# Adder.net
KiCad netlist of a schematic drawn in EAGLE
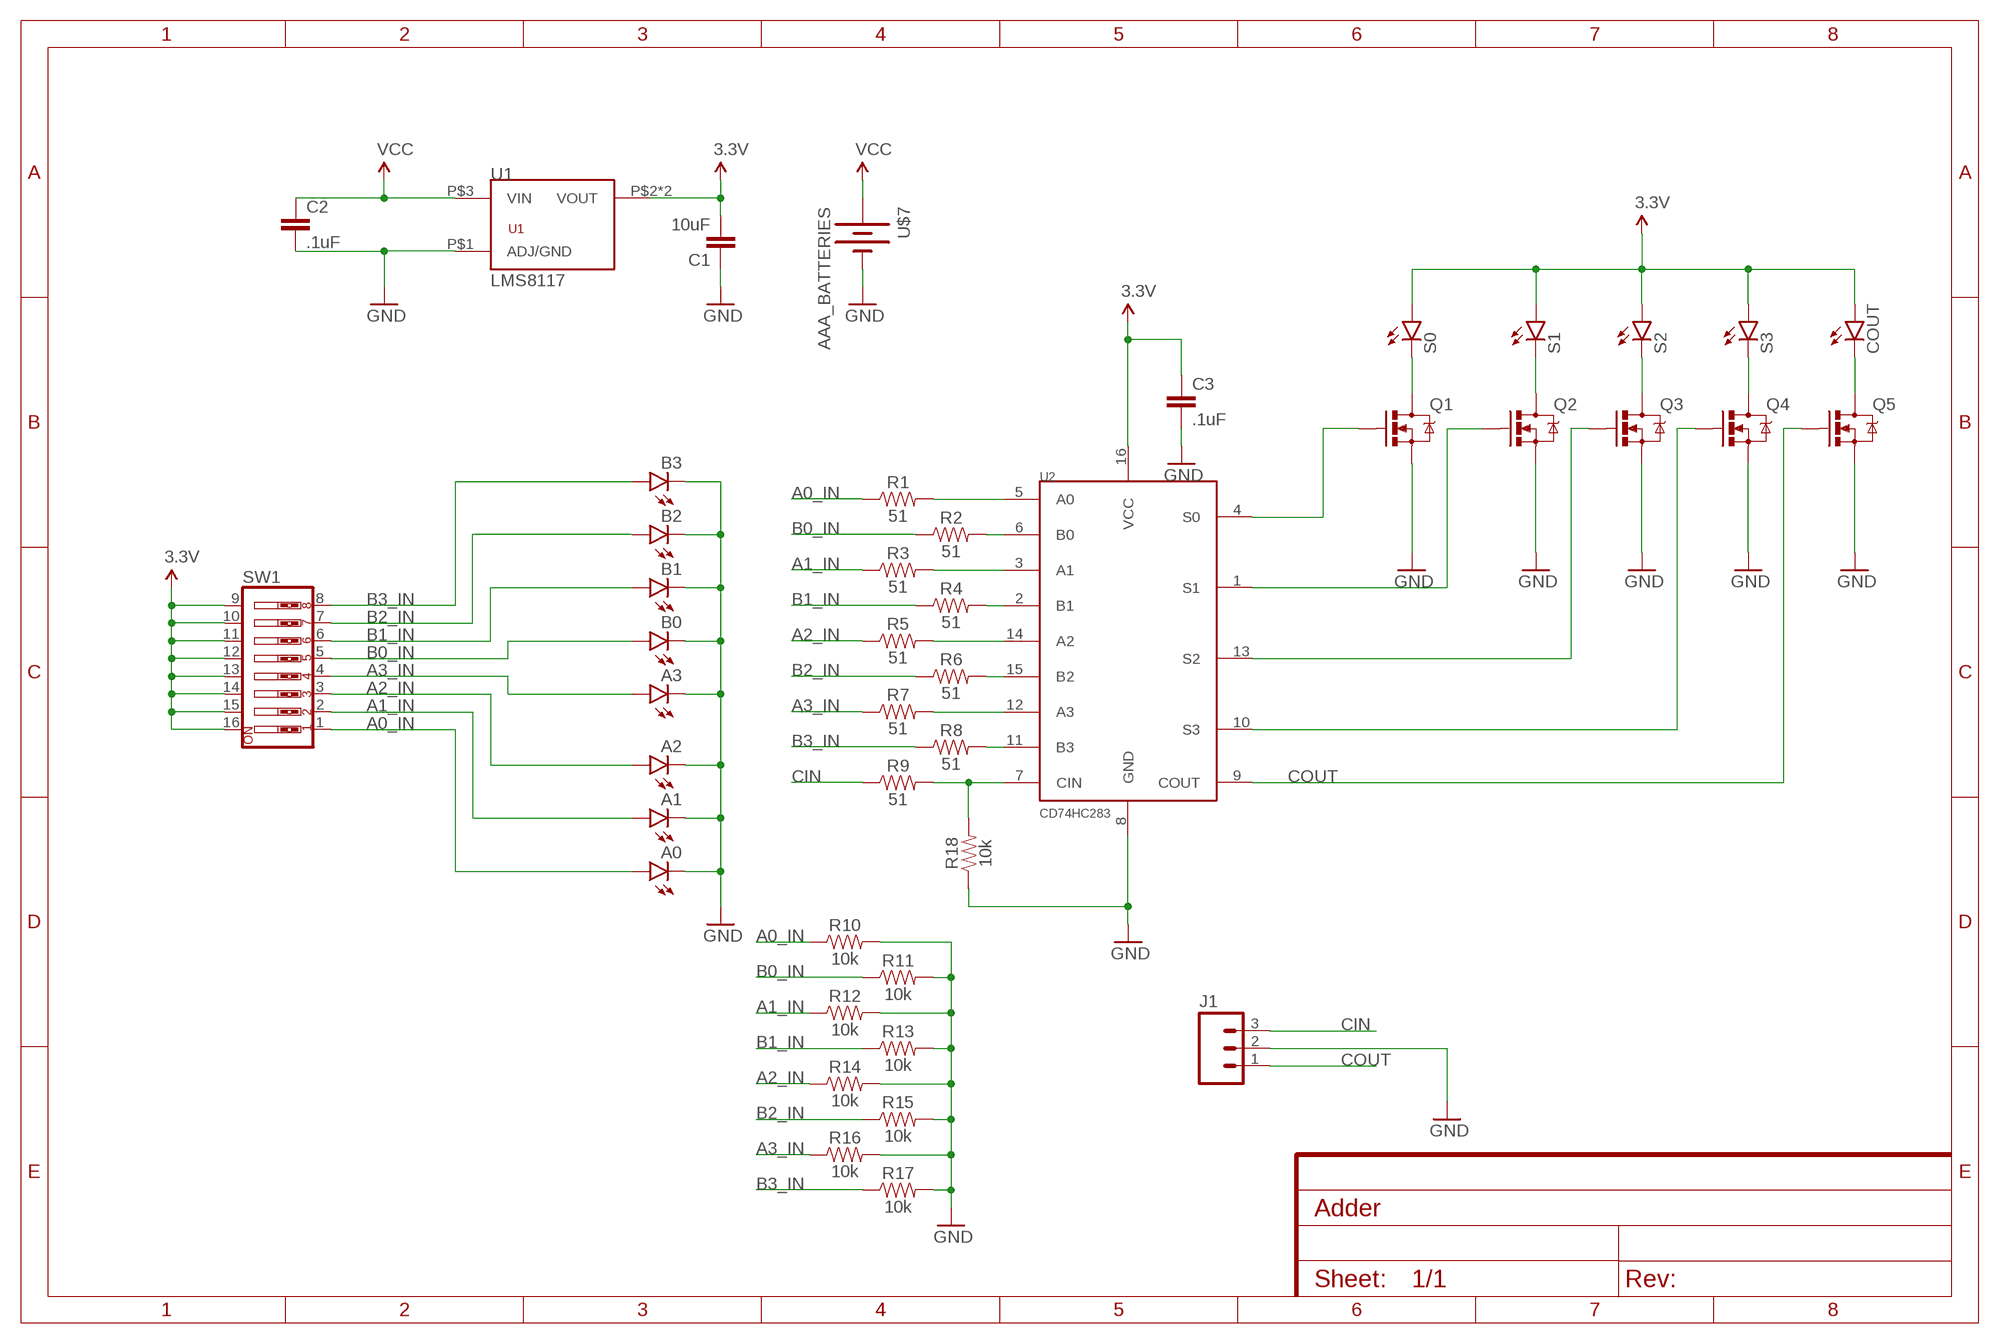
[diagram p0: schematic, sheet 1]

(export (version "E")
  (design (tool "Eeschema 10.0.6"))
  (components
    (comp (ref "A0")
      (value "LED5MM")
      (footprint "eagle-import:LED5MM")
      (libsource (lib "eagle-import") (part "LED5MM"))
    )
    (comp (ref "A1")
      (value "LED5MM")
      (footprint "eagle-import:LED5MM")
      (libsource (lib "eagle-import") (part "LED5MM"))
    )
    (comp (ref "A2")
      (value "LED5MM")
      (footprint "eagle-import:LED5MM")
      (libsource (lib "eagle-import") (part "LED5MM"))
    )
    (comp (ref "A3")
      (value "LED5MM")
      (footprint "eagle-import:LED5MM")
      (libsource (lib "eagle-import") (part "LED5MM"))
    )
    (comp (ref "B0")
      (value "LED5MM")
      (footprint "eagle-import:LED5MM")
      (libsource (lib "eagle-import") (part "LED5MM"))
    )
    (comp (ref "B1")
      (value "LED5MM")
      (footprint "eagle-import:LED5MM")
      (libsource (lib "eagle-import") (part "LED5MM"))
    )
    (comp (ref "B2")
      (value "LED5MM")
      (footprint "eagle-import:LED5MM")
      (libsource (lib "eagle-import") (part "LED5MM"))
    )
    (comp (ref "B3")
      (value "LED5MM")
      (footprint "eagle-import:LED5MM")
      (libsource (lib "eagle-import") (part "LED5MM"))
    )
    (comp (ref "C1")
      (value "10uF")
      (footprint "eagle-import:0603-CAP")
      (libsource (lib "eagle-import") (part "CAP0603-CAP"))
    )
    (comp (ref "C2")
      (value ".1uF")
      (footprint "eagle-import:0603-CAP")
      (libsource (lib "eagle-import") (part "CAP0603-CAP"))
    )
    (comp (ref "C3")
      (value ".1uF")
      (footprint "eagle-import:0603-CAP")
      (libsource (lib "eagle-import") (part "CAP0603-CAP"))
    )
    (comp (ref "COUT")
      (value "LED5MM")
      (footprint "eagle-import:LED5MM")
      (libsource (lib "eagle-import") (part "LED5MM"))
    )
    (comp (ref "J1")
      (value "M03PTH")
      (footprint "eagle-import:1X03")
      (libsource (lib "eagle-import") (part "M03PTH"))
    )
    (comp (ref "Q1")
      (value "MOSFET-NCHANNEL2N7000")
      (footprint "eagle-import:TO-92")
      (libsource (lib "eagle-import") (part "MOSFET-NCHANNEL2N7000"))
    )
    (comp (ref "Q2")
      (value "MOSFET-NCHANNEL2N7000")
      (footprint "eagle-import:TO-92")
      (libsource (lib "eagle-import") (part "MOSFET-NCHANNEL2N7000"))
    )
    (comp (ref "Q3")
      (value "MOSFET-NCHANNEL2N7000")
      (footprint "eagle-import:TO-92")
      (libsource (lib "eagle-import") (part "MOSFET-NCHANNEL2N7000"))
    )
    (comp (ref "Q4")
      (value "MOSFET-NCHANNEL2N7000")
      (footprint "eagle-import:TO-92")
      (libsource (lib "eagle-import") (part "MOSFET-NCHANNEL2N7000"))
    )
    (comp (ref "Q5")
      (value "MOSFET-NCHANNEL2N7000")
      (footprint "eagle-import:TO-92")
      (libsource (lib "eagle-import") (part "MOSFET-NCHANNEL2N7000"))
    )
    (comp (ref "R1")
      (value "51")
      (footprint "eagle-import:0805")
      (libsource (lib "eagle-import") (part "RESISTOR0805"))
    )
    (comp (ref "R2")
      (value "51")
      (footprint "eagle-import:0805")
      (libsource (lib "eagle-import") (part "RESISTOR0805"))
    )
    (comp (ref "R3")
      (value "51")
      (footprint "eagle-import:0805")
      (libsource (lib "eagle-import") (part "RESISTOR0805"))
    )
    (comp (ref "R4")
      (value "51")
      (footprint "eagle-import:0805")
      (libsource (lib "eagle-import") (part "RESISTOR0805"))
    )
    (comp (ref "R5")
      (value "51")
      (footprint "eagle-import:0805")
      (libsource (lib "eagle-import") (part "RESISTOR0805"))
    )
    (comp (ref "R6")
      (value "51")
      (footprint "eagle-import:0805")
      (libsource (lib "eagle-import") (part "RESISTOR0805"))
    )
    (comp (ref "R7")
      (value "51")
      (footprint "eagle-import:0805")
      (libsource (lib "eagle-import") (part "RESISTOR0805"))
    )
    (comp (ref "R8")
      (value "51")
      (footprint "eagle-import:0805")
      (libsource (lib "eagle-import") (part "RESISTOR0805"))
    )
    (comp (ref "R9")
      (value "51")
      (footprint "eagle-import:0805")
      (libsource (lib "eagle-import") (part "RESISTOR0805"))
    )
    (comp (ref "R10")
      (value "10k")
      (footprint "eagle-import:0805")
      (libsource (lib "eagle-import") (part "RESISTOR0805"))
    )
    (comp (ref "R11")
      (value "10k")
      (footprint "eagle-import:0805")
      (libsource (lib "eagle-import") (part "RESISTOR0805"))
    )
    (comp (ref "R12")
      (value "10k")
      (footprint "eagle-import:0805")
      (libsource (lib "eagle-import") (part "RESISTOR0805"))
    )
    (comp (ref "R13")
      (value "10k")
      (footprint "eagle-import:0805")
      (libsource (lib "eagle-import") (part "RESISTOR0805"))
    )
    (comp (ref "R14")
      (value "10k")
      (footprint "eagle-import:0805")
      (libsource (lib "eagle-import") (part "RESISTOR0805"))
    )
    (comp (ref "R15")
      (value "10k")
      (footprint "eagle-import:0805")
      (libsource (lib "eagle-import") (part "RESISTOR0805"))
    )
    (comp (ref "R16")
      (value "10k")
      (footprint "eagle-import:0805")
      (libsource (lib "eagle-import") (part "RESISTOR0805"))
    )
    (comp (ref "R17")
      (value "10k")
      (footprint "eagle-import:0805")
      (libsource (lib "eagle-import") (part "RESISTOR0805"))
    )
    (comp (ref "R18")
      (value "10k")
      (footprint "eagle-import:0805")
      (libsource (lib "eagle-import") (part "RESISTOR0805"))
    )
    (comp (ref "S0")
      (value "LED5MM")
      (footprint "eagle-import:LED5MM")
      (libsource (lib "eagle-import") (part "LED5MM"))
    )
    (comp (ref "S1")
      (value "LED5MM")
      (footprint "eagle-import:LED5MM")
      (libsource (lib "eagle-import") (part "LED5MM"))
    )
    (comp (ref "S2")
      (value "LED5MM")
      (footprint "eagle-import:LED5MM")
      (libsource (lib "eagle-import") (part "LED5MM"))
    )
    (comp (ref "S3")
      (value "LED5MM")
      (footprint "eagle-import:LED5MM")
      (libsource (lib "eagle-import") (part "LED5MM"))
    )
    (comp (ref "SW1")
      (value "SW_DIP-8")
      (footprint "eagle-import:DIPSWITCH-08")
      (libsource (lib "eagle-import") (part "SW_DIP-8"))
    )
    (comp (ref "U$7")
      (value "AAA_BATTERIES")
      (footprint "eagle-import:WIRE_LEADS")
      (libsource (lib "eagle-import") (part "AAA_BATTERIES"))
    )
    (comp (ref "U1")
      (value "LMS8117")
      (footprint "eagle-import:SOT-223")
      (libsource (lib "eagle-import") (part "LMS8117"))
    )
    (comp (ref "U2")
      (value "CD74HC283")
      (footprint "eagle-import:SO016")
      (libsource (lib "eagle-import") (part "CD74HC283"))
    )
  )
  (nets
    (net (code "1") (name "/A0_IN") (class "Default")
      (node (ref "A0") (pin "A") (pinfunction "A_A") (pintype "passive"))
      (node (ref "R1") (pin "1") (pinfunction "1_1") (pintype "passive"))
      (node (ref "R10") (pin "1") (pinfunction "1_1") (pintype "passive"))
      (node (ref "SW1") (pin "1") (pinfunction "1_1") (pintype "passive"))
    )
    (net (code "2") (name "/A1_IN") (class "Default")
      (node (ref "A1") (pin "A") (pinfunction "A_A") (pintype "passive"))
      (node (ref "R12") (pin "1") (pinfunction "1_1") (pintype "passive"))
      (node (ref "R3") (pin "1") (pinfunction "1_1") (pintype "passive"))
      (node (ref "SW1") (pin "2") (pinfunction "2_2") (pintype "passive"))
    )
    (net (code "3") (name "/A2_IN") (class "Default")
      (node (ref "A2") (pin "A") (pinfunction "A_A") (pintype "passive"))
      (node (ref "R14") (pin "1") (pinfunction "1_1") (pintype "passive"))
      (node (ref "R5") (pin "1") (pinfunction "1_1") (pintype "passive"))
      (node (ref "SW1") (pin "3") (pinfunction "3_3") (pintype "passive"))
    )
    (net (code "4") (name "/A3_IN") (class "Default")
      (node (ref "A3") (pin "A") (pinfunction "A_A") (pintype "passive"))
      (node (ref "R16") (pin "1") (pinfunction "1_1") (pintype "passive"))
      (node (ref "R7") (pin "1") (pinfunction "1_1") (pintype "passive"))
      (node (ref "SW1") (pin "4") (pinfunction "4_4") (pintype "passive"))
    )
    (net (code "5") (name "/B0_IN") (class "Default")
      (node (ref "B0") (pin "A") (pinfunction "A_A") (pintype "passive"))
      (node (ref "R11") (pin "1") (pinfunction "1_1") (pintype "passive"))
      (node (ref "R2") (pin "1") (pinfunction "1_1") (pintype "passive"))
      (node (ref "SW1") (pin "5") (pinfunction "5_5") (pintype "passive"))
    )
    (net (code "6") (name "/B1_IN") (class "Default")
      (node (ref "B1") (pin "A") (pinfunction "A_A") (pintype "passive"))
      (node (ref "R13") (pin "1") (pinfunction "1_1") (pintype "passive"))
      (node (ref "R4") (pin "1") (pinfunction "1_1") (pintype "passive"))
      (node (ref "SW1") (pin "6") (pinfunction "6_6") (pintype "passive"))
    )
    (net (code "7") (name "/B2_IN") (class "Default")
      (node (ref "B2") (pin "A") (pinfunction "A_A") (pintype "passive"))
      (node (ref "R15") (pin "1") (pinfunction "1_1") (pintype "passive"))
      (node (ref "R6") (pin "1") (pinfunction "1_1") (pintype "passive"))
      (node (ref "SW1") (pin "7") (pinfunction "7_7") (pintype "passive"))
    )
    (net (code "8") (name "/B3_IN") (class "Default")
      (node (ref "B3") (pin "A") (pinfunction "A_A") (pintype "passive"))
      (node (ref "R17") (pin "1") (pinfunction "1_1") (pintype "passive"))
      (node (ref "R8") (pin "1") (pinfunction "1_1") (pintype "passive"))
      (node (ref "SW1") (pin "8") (pinfunction "8_8") (pintype "passive"))
    )
    (net (code "9") (name "/CIN") (class "Default")
      (node (ref "J1") (pin "3") (pinfunction "3_3") (pintype "passive"))
      (node (ref "R9") (pin "1") (pinfunction "1_1") (pintype "passive"))
    )
    (net (code "10") (name "/COUT") (class "Default")
      (node (ref "J1") (pin "1") (pinfunction "1_1") (pintype "passive"))
      (node (ref "Q5") (pin "2") (pinfunction "G_2") (pintype "passive"))
      (node (ref "U2") (pin "9") (pinfunction "COUT_9") (pintype "bidirectional"))
    )
    (net (code "11") (name "3.3V") (class "Default")
      (node (ref "C1") (pin "2") (pinfunction "2_2") (pintype "passive"))
      (node (ref "C3") (pin "1") (pinfunction "1_1") (pintype "passive"))
      (node (ref "COUT") (pin "A") (pinfunction "A_A") (pintype "passive"))
      (node (ref "S0") (pin "A") (pinfunction "A_A") (pintype "passive"))
      (node (ref "S1") (pin "A") (pinfunction "A_A") (pintype "passive"))
      (node (ref "S2") (pin "A") (pinfunction "A_A") (pintype "passive"))
      (node (ref "S3") (pin "A") (pinfunction "A_A") (pintype "passive"))
      (node (ref "SW1") (pin "10") (pinfunction "10_10") (pintype "passive"))
      (node (ref "SW1") (pin "11") (pinfunction "11_11") (pintype "passive"))
      (node (ref "SW1") (pin "12") (pinfunction "12_12") (pintype "passive"))
      (node (ref "SW1") (pin "13") (pinfunction "13_13") (pintype "passive"))
      (node (ref "SW1") (pin "14") (pinfunction "14_14") (pintype "passive"))
      (node (ref "SW1") (pin "15") (pinfunction "15_15") (pintype "passive"))
      (node (ref "SW1") (pin "16") (pinfunction "16_16") (pintype "passive"))
      (node (ref "SW1") (pin "9") (pinfunction "9_9") (pintype "passive"))
      (node (ref "U1") (pin "P$2") (pinfunction "VOUT_P$2") (pintype "bidirectional"))
      (node (ref "U1") (pin "P$4") (pinfunction "VOUT_P$4") (pintype "bidirectional"))
      (node (ref "U2") (pin "16") (pinfunction "VCC_16") (pintype "bidirectional"))
    )
    (net (code "12") (name "GND") (class "Default")
      (node (ref "A0") (pin "K") (pinfunction "C_K") (pintype "passive"))
      (node (ref "A1") (pin "K") (pinfunction "C_K") (pintype "passive"))
      (node (ref "A2") (pin "K") (pinfunction "C_K") (pintype "passive"))
      (node (ref "A3") (pin "K") (pinfunction "C_K") (pintype "passive"))
      (node (ref "B0") (pin "K") (pinfunction "C_K") (pintype "passive"))
      (node (ref "B1") (pin "K") (pinfunction "C_K") (pintype "passive"))
      (node (ref "B2") (pin "K") (pinfunction "C_K") (pintype "passive"))
      (node (ref "B3") (pin "K") (pinfunction "C_K") (pintype "passive"))
      (node (ref "C1") (pin "1") (pinfunction "1_1") (pintype "passive"))
      (node (ref "C2") (pin "2") (pinfunction "2_2") (pintype "passive"))
      (node (ref "C3") (pin "2") (pinfunction "2_2") (pintype "passive"))
      (node (ref "J1") (pin "2") (pinfunction "2_2") (pintype "passive"))
      (node (ref "Q1") (pin "1") (pinfunction "S_1") (pintype "passive"))
      (node (ref "Q2") (pin "1") (pinfunction "S_1") (pintype "passive"))
      (node (ref "Q3") (pin "1") (pinfunction "S_1") (pintype "passive"))
      (node (ref "Q4") (pin "1") (pinfunction "S_1") (pintype "passive"))
      (node (ref "Q5") (pin "1") (pinfunction "S_1") (pintype "passive"))
      (node (ref "R10") (pin "2") (pinfunction "2_2") (pintype "passive"))
      (node (ref "R11") (pin "2") (pinfunction "2_2") (pintype "passive"))
      (node (ref "R12") (pin "2") (pinfunction "2_2") (pintype "passive"))
      (node (ref "R13") (pin "2") (pinfunction "2_2") (pintype "passive"))
      (node (ref "R14") (pin "2") (pinfunction "2_2") (pintype "passive"))
      (node (ref "R15") (pin "2") (pinfunction "2_2") (pintype "passive"))
      (node (ref "R16") (pin "2") (pinfunction "2_2") (pintype "passive"))
      (node (ref "R17") (pin "2") (pinfunction "2_2") (pintype "passive"))
      (node (ref "R18") (pin "1") (pinfunction "1_1") (pintype "passive"))
      (node (ref "U$7") (pin "P$1") (pinfunction "-_P$1") (pintype "power_in"))
      (node (ref "U1") (pin "P$1") (pinfunction "ADJ/GND_P$1") (pintype "bidirectional"))
      (node (ref "U2") (pin "8") (pinfunction "GND_8") (pintype "bidirectional"))
    )
    (net (code "13") (name "Net-(COUT-C)") (class "Default")
      (node (ref "COUT") (pin "K") (pinfunction "C_K") (pintype "passive"))
      (node (ref "Q5") (pin "3") (pinfunction "D_3") (pintype "passive"))
    )
    (net (code "14") (name "Net-(Q1-D)") (class "Default")
      (node (ref "Q1") (pin "3") (pinfunction "D_3") (pintype "passive"))
      (node (ref "S0") (pin "K") (pinfunction "C_K") (pintype "passive"))
    )
    (net (code "15") (name "Net-(Q1-G)") (class "Default")
      (node (ref "Q1") (pin "2") (pinfunction "G_2") (pintype "passive"))
      (node (ref "U2") (pin "4") (pinfunction "S0_4") (pintype "bidirectional"))
    )
    (net (code "16") (name "Net-(Q2-D)") (class "Default")
      (node (ref "Q2") (pin "3") (pinfunction "D_3") (pintype "passive"))
      (node (ref "S1") (pin "K") (pinfunction "C_K") (pintype "passive"))
    )
    (net (code "17") (name "Net-(Q2-G)") (class "Default")
      (node (ref "Q2") (pin "2") (pinfunction "G_2") (pintype "passive"))
      (node (ref "U2") (pin "1") (pinfunction "S1_1") (pintype "bidirectional"))
    )
    (net (code "18") (name "Net-(Q3-D)") (class "Default")
      (node (ref "Q3") (pin "3") (pinfunction "D_3") (pintype "passive"))
      (node (ref "S2") (pin "K") (pinfunction "C_K") (pintype "passive"))
    )
    (net (code "19") (name "Net-(Q3-G)") (class "Default")
      (node (ref "Q3") (pin "2") (pinfunction "G_2") (pintype "passive"))
      (node (ref "U2") (pin "13") (pinfunction "S2_13") (pintype "bidirectional"))
    )
    (net (code "20") (name "Net-(Q4-D)") (class "Default")
      (node (ref "Q4") (pin "3") (pinfunction "D_3") (pintype "passive"))
      (node (ref "S3") (pin "K") (pinfunction "C_K") (pintype "passive"))
    )
    (net (code "21") (name "Net-(Q4-G)") (class "Default")
      (node (ref "Q4") (pin "2") (pinfunction "G_2") (pintype "passive"))
      (node (ref "U2") (pin "10") (pinfunction "S3_10") (pintype "bidirectional"))
    )
    (net (code "22") (name "Net-(U2-A0)") (class "Default")
      (node (ref "R1") (pin "2") (pinfunction "2_2") (pintype "passive"))
      (node (ref "U2") (pin "5") (pinfunction "A0_5") (pintype "bidirectional"))
    )
    (net (code "23") (name "Net-(U2-A1)") (class "Default")
      (node (ref "R3") (pin "2") (pinfunction "2_2") (pintype "passive"))
      (node (ref "U2") (pin "3") (pinfunction "A1_3") (pintype "bidirectional"))
    )
    (net (code "24") (name "Net-(U2-A2)") (class "Default")
      (node (ref "R5") (pin "2") (pinfunction "2_2") (pintype "passive"))
      (node (ref "U2") (pin "14") (pinfunction "A2_14") (pintype "bidirectional"))
    )
    (net (code "25") (name "Net-(U2-A3)") (class "Default")
      (node (ref "R7") (pin "2") (pinfunction "2_2") (pintype "passive"))
      (node (ref "U2") (pin "12") (pinfunction "A3_12") (pintype "bidirectional"))
    )
    (net (code "26") (name "Net-(U2-B0)") (class "Default")
      (node (ref "R2") (pin "2") (pinfunction "2_2") (pintype "passive"))
      (node (ref "U2") (pin "6") (pinfunction "B0_6") (pintype "bidirectional"))
    )
    (net (code "27") (name "Net-(U2-B1)") (class "Default")
      (node (ref "R4") (pin "2") (pinfunction "2_2") (pintype "passive"))
      (node (ref "U2") (pin "2") (pinfunction "B1_2") (pintype "bidirectional"))
    )
    (net (code "28") (name "Net-(U2-B2)") (class "Default")
      (node (ref "R6") (pin "2") (pinfunction "2_2") (pintype "passive"))
      (node (ref "U2") (pin "15") (pinfunction "B2_15") (pintype "bidirectional"))
    )
    (net (code "29") (name "Net-(U2-B3)") (class "Default")
      (node (ref "R8") (pin "2") (pinfunction "2_2") (pintype "passive"))
      (node (ref "U2") (pin "11") (pinfunction "B3_11") (pintype "bidirectional"))
    )
    (net (code "30") (name "Net-(U2-CIN)") (class "Default")
      (node (ref "R18") (pin "2") (pinfunction "2_2") (pintype "passive"))
      (node (ref "R9") (pin "2") (pinfunction "2_2") (pintype "passive"))
      (node (ref "U2") (pin "7") (pinfunction "CIN_7") (pintype "bidirectional"))
    )
    (net (code "31") (name "VCC") (class "Default")
      (node (ref "C2") (pin "1") (pinfunction "1_1") (pintype "passive"))
      (node (ref "U$7") (pin "P$2") (pinfunction "+_P$2") (pintype "power_in"))
      (node (ref "U1") (pin "P$3") (pinfunction "VIN_P$3") (pintype "bidirectional"))
    )
  )
)
